# hijack_jtag_a.net
KiCad netlist of a schematic drawn in EAGLE
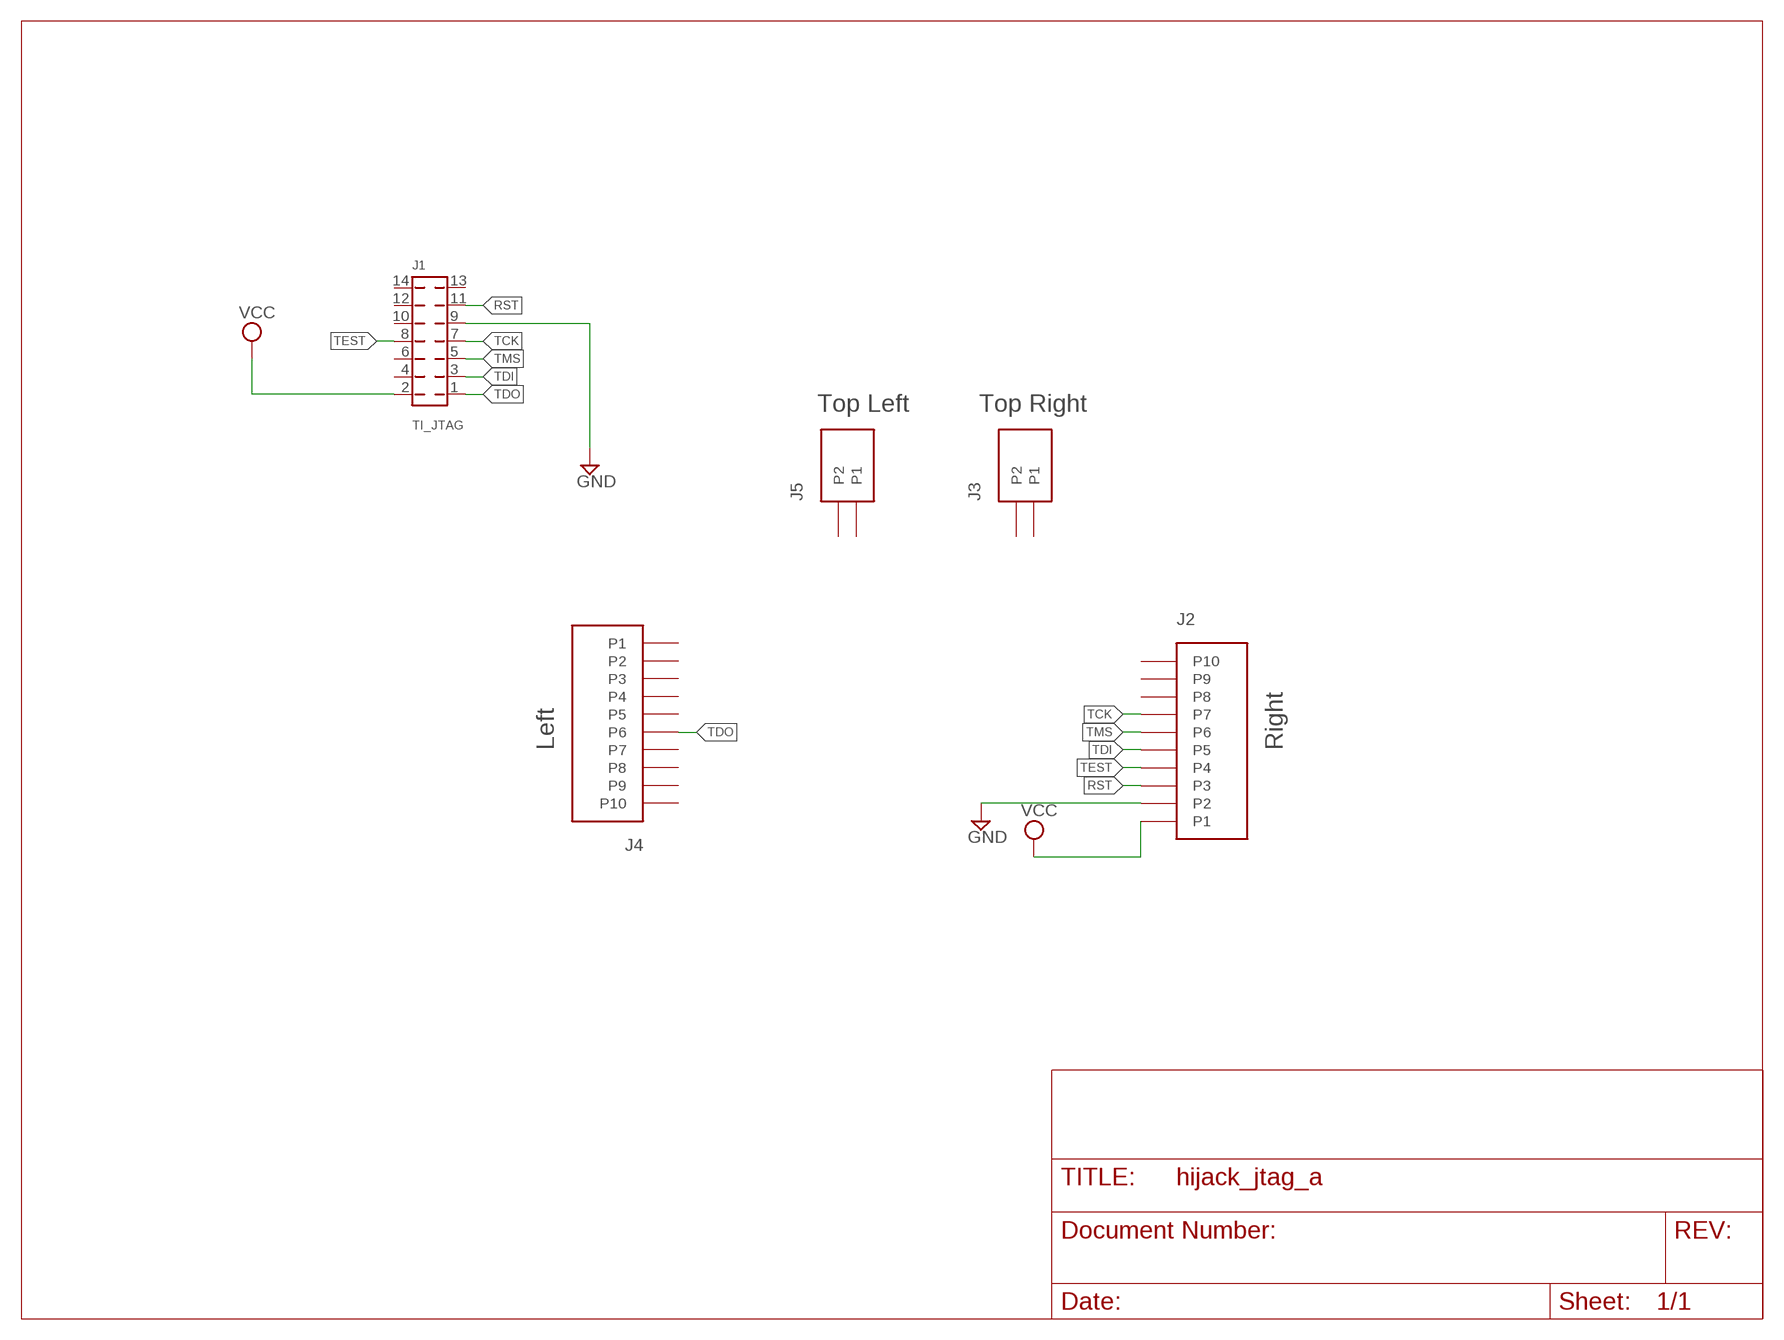
[diagram p0: schematic, sheet 1]

(export (version "E")
  (design (tool "Eeschema 10.0.6"))
  (components
    (comp (ref "J1")
      (value "TI_JTAG")
      (footprint "eagle-import:TST-107")
      (libsource (lib "eagle-import") (part "TI_JTAG"))
    )
    (comp (ref "J2")
      (value "HEADER10POS")
      (footprint "eagle-import:10PIN2MMHEADER")
      (libsource (lib "eagle-import") (part "HEADER10POS"))
    )
    (comp (ref "J3")
      (value "HEADER2POS")
      (footprint "eagle-import:2PIN2MMHEADER")
      (libsource (lib "eagle-import") (part "HEADER2POS"))
    )
    (comp (ref "J4")
      (value "HEADER10POS")
      (footprint "eagle-import:10PIN2MMHEADER")
      (libsource (lib "eagle-import") (part "HEADER10POS"))
    )
    (comp (ref "J5")
      (value "HEADER2POS")
      (footprint "eagle-import:2PIN2MMHEADER")
      (libsource (lib "eagle-import") (part "HEADER2POS"))
    )
  )
  (nets
    (net (code "1") (name "GND") (class "Default")
      (node (ref "J1") (pin "9") (pinfunction "P$9_9") (pintype "bidirectional"))
      (node (ref "J2") (pin "P2") (pinfunction "P2_P2") (pintype "bidirectional"))
    )
    (net (code "2") (name "RST") (class "Default")
      (node (ref "J1") (pin "11") (pinfunction "P$11_11") (pintype "bidirectional"))
      (node (ref "J2") (pin "P3") (pinfunction "P3_P3") (pintype "bidirectional"))
    )
    (net (code "3") (name "TCK") (class "Default")
      (node (ref "J1") (pin "7") (pinfunction "P$7_7") (pintype "bidirectional"))
      (node (ref "J2") (pin "P7") (pinfunction "P7_P7") (pintype "bidirectional"))
    )
    (net (code "4") (name "TDI") (class "Default")
      (node (ref "J1") (pin "3") (pinfunction "P$3_3") (pintype "bidirectional"))
      (node (ref "J2") (pin "P5") (pinfunction "P5_P5") (pintype "bidirectional"))
    )
    (net (code "5") (name "TDO") (class "Default")
      (node (ref "J1") (pin "1") (pinfunction "P$1_1") (pintype "bidirectional"))
      (node (ref "J4") (pin "P6") (pinfunction "P6_P6") (pintype "bidirectional"))
    )
    (net (code "6") (name "TEST") (class "Default")
      (node (ref "J1") (pin "8") (pinfunction "P$8_8") (pintype "bidirectional"))
      (node (ref "J2") (pin "P4") (pinfunction "P4_P4") (pintype "bidirectional"))
    )
    (net (code "7") (name "TMS") (class "Default")
      (node (ref "J1") (pin "5") (pinfunction "P$5_5") (pintype "bidirectional"))
      (node (ref "J2") (pin "P6") (pinfunction "P6_P6") (pintype "bidirectional"))
    )
    (net (code "8") (name "VCC") (class "Default")
      (node (ref "J1") (pin "2") (pinfunction "P$2_2") (pintype "bidirectional"))
      (node (ref "J2") (pin "P1") (pinfunction "P1_P1") (pintype "bidirectional"))
    )
    (net (code "9") (name "unconnected-(J1-P$4-Pad4)") (class "Default")
      (node (ref "J1") (pin "4") (pinfunction "P$4_4") (pintype "bidirectional"))
    )
    (net (code "10") (name "unconnected-(J1-P$6-Pad6)") (class "Default")
      (node (ref "J1") (pin "6") (pinfunction "P$6_6") (pintype "bidirectional"))
    )
    (net (code "11") (name "unconnected-(J1-P$10-Pad10)") (class "Default")
      (node (ref "J1") (pin "10") (pinfunction "P$10_10") (pintype "bidirectional"))
    )
    (net (code "12") (name "unconnected-(J1-P$12-Pad12)") (class "Default")
      (node (ref "J1") (pin "12") (pinfunction "P$12_12") (pintype "bidirectional"))
    )
    (net (code "13") (name "unconnected-(J1-P$13-Pad13)") (class "Default")
      (node (ref "J1") (pin "13") (pinfunction "P$13_13") (pintype "bidirectional"))
    )
    (net (code "14") (name "unconnected-(J1-P$14-Pad14)") (class "Default")
      (node (ref "J1") (pin "14") (pinfunction "P$14_14") (pintype "bidirectional"))
    )
    (net (code "15") (name "unconnected-(J2-PadP8)") (class "Default")
      (node (ref "J2") (pin "P8") (pinfunction "P8_P8") (pintype "bidirectional"))
    )
    (net (code "16") (name "unconnected-(J2-PadP9)") (class "Default")
      (node (ref "J2") (pin "P9") (pinfunction "P9_P9") (pintype "bidirectional"))
    )
    (net (code "17") (name "unconnected-(J2-PadP10)") (class "Default")
      (node (ref "J2") (pin "P10") (pinfunction "P10_P10") (pintype "bidirectional"))
    )
    (net (code "18") (name "unconnected-(J3-PadP1)") (class "Default")
      (node (ref "J3") (pin "P1") (pinfunction "P1_P1") (pintype "bidirectional"))
    )
    (net (code "19") (name "unconnected-(J3-PadP2)") (class "Default")
      (node (ref "J3") (pin "P2") (pinfunction "P2_P2") (pintype "bidirectional"))
    )
    (net (code "20") (name "unconnected-(J4-PadP1)") (class "Default")
      (node (ref "J4") (pin "P1") (pinfunction "P1_P1") (pintype "bidirectional"))
    )
    (net (code "21") (name "unconnected-(J4-PadP2)") (class "Default")
      (node (ref "J4") (pin "P2") (pinfunction "P2_P2") (pintype "bidirectional"))
    )
    (net (code "22") (name "unconnected-(J4-PadP3)") (class "Default")
      (node (ref "J4") (pin "P3") (pinfunction "P3_P3") (pintype "bidirectional"))
    )
    (net (code "23") (name "unconnected-(J4-PadP4)") (class "Default")
      (node (ref "J4") (pin "P4") (pinfunction "P4_P4") (pintype "bidirectional"))
    )
    (net (code "24") (name "unconnected-(J4-PadP5)") (class "Default")
      (node (ref "J4") (pin "P5") (pinfunction "P5_P5") (pintype "bidirectional"))
    )
    (net (code "25") (name "unconnected-(J4-PadP7)") (class "Default")
      (node (ref "J4") (pin "P7") (pinfunction "P7_P7") (pintype "bidirectional"))
    )
    (net (code "26") (name "unconnected-(J4-PadP8)") (class "Default")
      (node (ref "J4") (pin "P8") (pinfunction "P8_P8") (pintype "bidirectional"))
    )
    (net (code "27") (name "unconnected-(J4-PadP9)") (class "Default")
      (node (ref "J4") (pin "P9") (pinfunction "P9_P9") (pintype "bidirectional"))
    )
    (net (code "28") (name "unconnected-(J4-PadP10)") (class "Default")
      (node (ref "J4") (pin "P10") (pinfunction "P10_P10") (pintype "bidirectional"))
    )
    (net (code "29") (name "unconnected-(J5-PadP1)") (class "Default")
      (node (ref "J5") (pin "P1") (pinfunction "P1_P1") (pintype "bidirectional"))
    )
    (net (code "30") (name "unconnected-(J5-PadP2)") (class "Default")
      (node (ref "J5") (pin "P2") (pinfunction "P2_P2") (pintype "bidirectional"))
    )
  )
)
